# W5500_Ethernet_shield.net
KiCad netlist of a schematic drawn in EAGLE
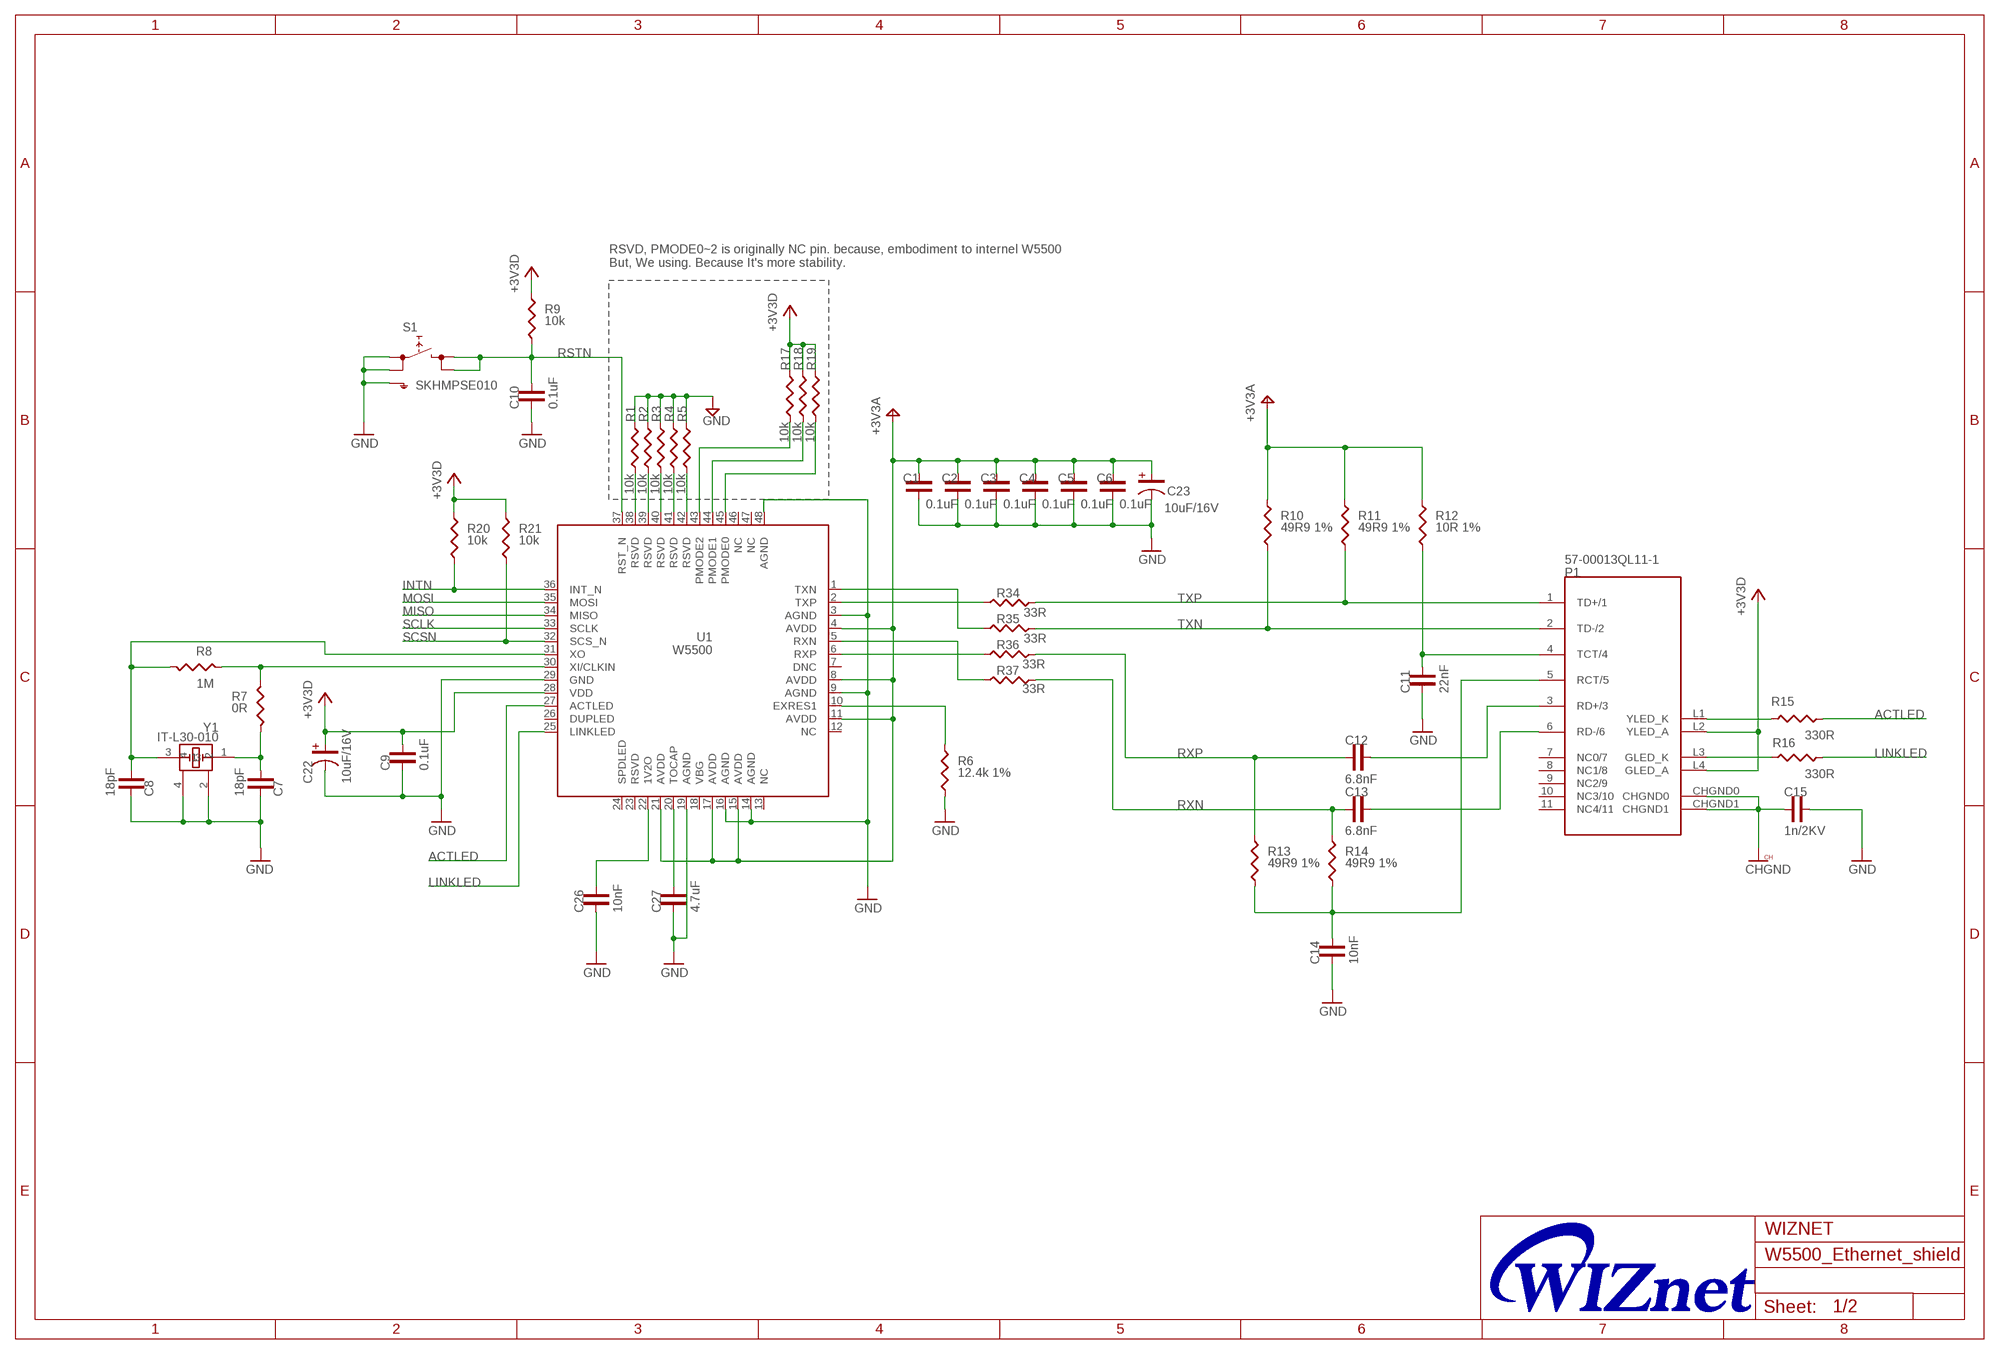
[diagram p0: schematic, sheet 1]
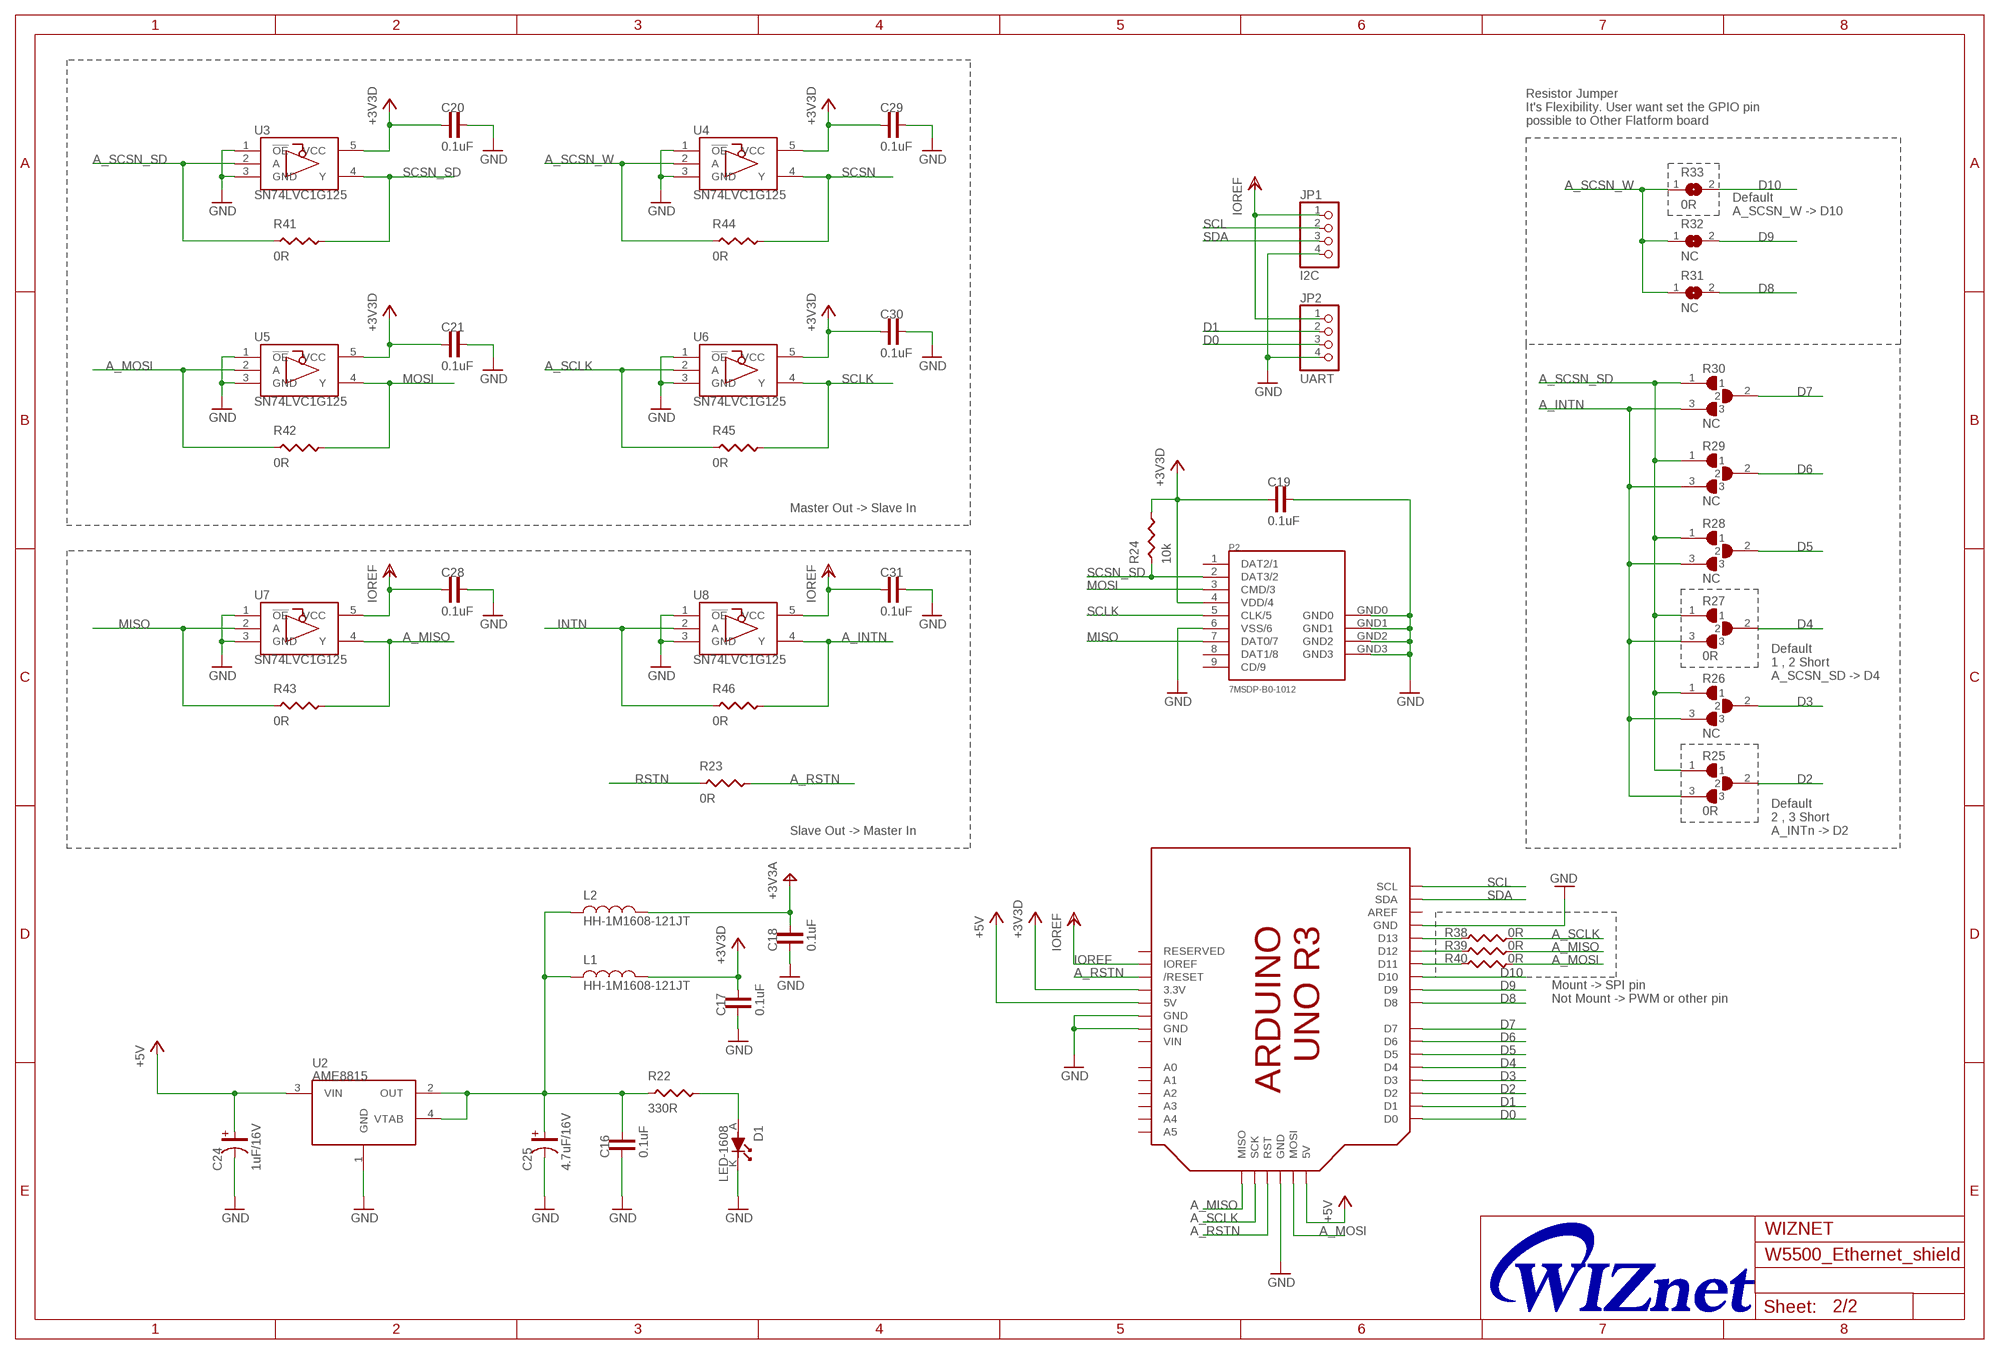
[diagram p1: schematic, sheet 2]

(export (version "E")
  (design (tool "Eeschema 10.0.6"))
  (components
    (comp (ref "C1")
      (value "0.1uF")
      (footprint "eagle-import:C-1608")
      (libsource (lib "eagle-import") (part "C-1608"))
    )
    (comp (ref "C2")
      (value "0.1uF")
      (footprint "eagle-import:C-1608")
      (libsource (lib "eagle-import") (part "C-1608"))
    )
    (comp (ref "C3")
      (value "0.1uF")
      (footprint "eagle-import:C-1608")
      (libsource (lib "eagle-import") (part "C-1608"))
    )
    (comp (ref "C4")
      (value "0.1uF")
      (footprint "eagle-import:C-1608")
      (libsource (lib "eagle-import") (part "C-1608"))
    )
    (comp (ref "C5")
      (value "0.1uF")
      (footprint "eagle-import:C-1608")
      (libsource (lib "eagle-import") (part "C-1608"))
    )
    (comp (ref "C6")
      (value "0.1uF")
      (footprint "eagle-import:C-1608")
      (libsource (lib "eagle-import") (part "C-1608"))
    )
    (comp (ref "C7")
      (value "18pF")
      (footprint "eagle-import:C-1608")
      (libsource (lib "eagle-import") (part "C-1608"))
    )
    (comp (ref "C8")
      (value "18pF")
      (footprint "eagle-import:C-1608")
      (libsource (lib "eagle-import") (part "C-1608"))
    )
    (comp (ref "C9")
      (value "0.1uF")
      (footprint "eagle-import:C-1608")
      (libsource (lib "eagle-import") (part "C-1608"))
    )
    (comp (ref "C10")
      (value "0.1uF")
      (footprint "eagle-import:C-1608")
      (libsource (lib "eagle-import") (part "C-1608"))
    )
    (comp (ref "C11")
      (value "22nF")
      (footprint "eagle-import:C-1608")
      (libsource (lib "eagle-import") (part "C-1608"))
    )
    (comp (ref "C12")
      (value "6.8nF")
      (footprint "eagle-import:C-1608")
      (libsource (lib "eagle-import") (part "C-1608"))
    )
    (comp (ref "C13")
      (value "6.8nF")
      (footprint "eagle-import:C-1608")
      (libsource (lib "eagle-import") (part "C-1608"))
    )
    (comp (ref "C14")
      (value "10nF")
      (footprint "eagle-import:C-1608")
      (libsource (lib "eagle-import") (part "C-1608"))
    )
    (comp (ref "C15")
      (value "1n/2KV")
      (footprint "eagle-import:C-1808")
      (libsource (lib "eagle-import") (part "C-1808"))
    )
    (comp (ref "C22")
      (value "10uF/16V")
      (footprint "eagle-import:C-3216(TANTAL)")
      (libsource (lib "eagle-import") (part "C-3216(TANTAL)"))
    )
    (comp (ref "C23")
      (value "10uF/16V")
      (footprint "eagle-import:C-3216(TANTAL)")
      (libsource (lib "eagle-import") (part "C-3216(TANTAL)"))
    )
    (comp (ref "C26")
      (value "10nF")
      (footprint "eagle-import:C-1608")
      (libsource (lib "eagle-import") (part "C-1608"))
    )
    (comp (ref "C27")
      (value "4.7uF")
      (footprint "eagle-import:C-2012")
      (libsource (lib "eagle-import") (part "C-2012"))
    )
    (comp (ref "P1")
      (value "57-00013QL11-1")
      (footprint "eagle-import:57-00013QL11-1")
      (libsource (lib "eagle-import") (part "57-00013QL11-1"))
    )
    (comp (ref "R1")
      (value "10k")
      (footprint "eagle-import:R-1608")
      (libsource (lib "eagle-import") (part "R-1608"))
    )
    (comp (ref "R2")
      (value "10k")
      (footprint "eagle-import:R-1608")
      (libsource (lib "eagle-import") (part "R-1608"))
    )
    (comp (ref "R3")
      (value "10k")
      (footprint "eagle-import:R-1608")
      (libsource (lib "eagle-import") (part "R-1608"))
    )
    (comp (ref "R4")
      (value "10k")
      (footprint "eagle-import:R-1608")
      (libsource (lib "eagle-import") (part "R-1608"))
    )
    (comp (ref "R5")
      (value "10k")
      (footprint "eagle-import:R-1608")
      (libsource (lib "eagle-import") (part "R-1608"))
    )
    (comp (ref "R6")
      (value "12.4k 1%")
      (footprint "eagle-import:R-1608")
      (libsource (lib "eagle-import") (part "R-1608"))
    )
    (comp (ref "R7")
      (value "0R")
      (footprint "eagle-import:R-1608")
      (libsource (lib "eagle-import") (part "R-1608"))
    )
    (comp (ref "R8")
      (value "1M")
      (footprint "eagle-import:R-1608")
      (libsource (lib "eagle-import") (part "R-1608"))
    )
    (comp (ref "R9")
      (value "10k")
      (footprint "eagle-import:R-1608")
      (libsource (lib "eagle-import") (part "R-1608"))
    )
    (comp (ref "R10")
      (value "49R9 1%")
      (footprint "eagle-import:R-1608")
      (libsource (lib "eagle-import") (part "R-1608"))
    )
    (comp (ref "R11")
      (value "49R9 1%")
      (footprint "eagle-import:R-1608")
      (libsource (lib "eagle-import") (part "R-1608"))
    )
    (comp (ref "R12")
      (value "10R 1%")
      (footprint "eagle-import:R-1608")
      (libsource (lib "eagle-import") (part "R-1608"))
    )
    (comp (ref "R13")
      (value "49R9 1%")
      (footprint "eagle-import:R-1608")
      (libsource (lib "eagle-import") (part "R-1608"))
    )
    (comp (ref "R14")
      (value "49R9 1%")
      (footprint "eagle-import:R-1608")
      (libsource (lib "eagle-import") (part "R-1608"))
    )
    (comp (ref "R15")
      (value "330R")
      (footprint "eagle-import:R-1608")
      (libsource (lib "eagle-import") (part "R-1608"))
    )
    (comp (ref "R16")
      (value "330R")
      (footprint "eagle-import:R-1608")
      (libsource (lib "eagle-import") (part "R-1608"))
    )
    (comp (ref "R17")
      (value "10k")
      (footprint "eagle-import:R-1608")
      (libsource (lib "eagle-import") (part "R-1608"))
    )
    (comp (ref "R18")
      (value "10k")
      (footprint "eagle-import:R-1608")
      (libsource (lib "eagle-import") (part "R-1608"))
    )
    (comp (ref "R19")
      (value "10k")
      (footprint "eagle-import:R-1608")
      (libsource (lib "eagle-import") (part "R-1608"))
    )
    (comp (ref "R20")
      (value "10k")
      (footprint "eagle-import:R-1608")
      (libsource (lib "eagle-import") (part "R-1608"))
    )
    (comp (ref "R21")
      (value "10k")
      (footprint "eagle-import:R-1608")
      (libsource (lib "eagle-import") (part "R-1608"))
    )
    (comp (ref "R34")
      (value "33R")
      (footprint "eagle-import:R-1608")
      (libsource (lib "eagle-import") (part "R-1608"))
    )
    (comp (ref "R35")
      (value "33R")
      (footprint "eagle-import:R-1608")
      (libsource (lib "eagle-import") (part "R-1608"))
    )
    (comp (ref "R36")
      (value "33R")
      (footprint "eagle-import:R-1608")
      (libsource (lib "eagle-import") (part "R-1608"))
    )
    (comp (ref "R37")
      (value "33R")
      (footprint "eagle-import:R-1608")
      (libsource (lib "eagle-import") (part "R-1608"))
    )
    (comp (ref "S1")
      (value "SKHMPSE010")
      (footprint "eagle-import:SKHMPXE010")
      (libsource (lib "eagle-import") (part "SKHMPE010S"))
    )
    (comp (ref "U1")
      (value "W5500")
      (footprint "eagle-import:W5500")
      (libsource (lib "eagle-import") (part "W5500"))
    )
    (comp (ref "Y1")
      (value "IT-L30-010")
      (footprint "eagle-import:IT-L30-010")
      (libsource (lib "eagle-import") (part "IT-L30-010"))
    )
    (comp (ref "C16")
      (value "0.1uF")
      (footprint "eagle-import:C-1608")
      (libsource (lib "eagle-import") (part "C-1608"))
    )
    (comp (ref "C17")
      (value "0.1uF")
      (footprint "eagle-import:C-1608")
      (libsource (lib "eagle-import") (part "C-1608"))
    )
    (comp (ref "C18")
      (value "0.1uF")
      (footprint "eagle-import:C-1608")
      (libsource (lib "eagle-import") (part "C-1608"))
    )
    (comp (ref "C19")
      (value "0.1uF")
      (footprint "eagle-import:C-1608")
      (libsource (lib "eagle-import") (part "C-1608"))
    )
    (comp (ref "C20")
      (value "0.1uF")
      (footprint "eagle-import:C-1608")
      (libsource (lib "eagle-import") (part "C-1608"))
    )
    (comp (ref "C21")
      (value "0.1uF")
      (footprint "eagle-import:C-1608")
      (libsource (lib "eagle-import") (part "C-1608"))
    )
    (comp (ref "C24")
      (value "1uF/16V")
      (footprint "eagle-import:C-3216(TANTAL)")
      (libsource (lib "eagle-import") (part "C-3216(TANTAL)"))
    )
    (comp (ref "C25")
      (value "4.7uF/16V")
      (footprint "eagle-import:C-3216(TANTAL)")
      (libsource (lib "eagle-import") (part "C-3216(TANTAL)"))
    )
    (comp (ref "C28")
      (value "0.1uF")
      (footprint "eagle-import:C-1608")
      (libsource (lib "eagle-import") (part "C-1608"))
    )
    (comp (ref "C29")
      (value "0.1uF")
      (footprint "eagle-import:C-1608")
      (libsource (lib "eagle-import") (part "C-1608"))
    )
    (comp (ref "C30")
      (value "0.1uF")
      (footprint "eagle-import:C-1608")
      (libsource (lib "eagle-import") (part "C-1608"))
    )
    (comp (ref "C31")
      (value "0.1uF")
      (footprint "eagle-import:C-1608")
      (libsource (lib "eagle-import") (part "C-1608"))
    )
    (comp (ref "D1")
      (value "LED-1608")
      (footprint "eagle-import:LED-1608")
      (libsource (lib "eagle-import") (part "LED-1608"))
    )
    (comp (ref "JP1")
      (value "I2C")
      (footprint "eagle-import:1X04")
      (libsource (lib "eagle-import") (part "PINHD-1X4"))
    )
    (comp (ref "JP2")
      (value "UART")
      (footprint "eagle-import:1X04")
      (libsource (lib "eagle-import") (part "PINHD-1X4"))
    )
    (comp (ref "L1")
      (value "HH-1M1608-121JT")
      (footprint "eagle-import:L-1608")
      (libsource (lib "eagle-import") (part "L-1608"))
    )
    (comp (ref "L2")
      (value "HH-1M1608-121JT")
      (footprint "eagle-import:L-1608")
      (libsource (lib "eagle-import") (part "L-1608"))
    )
    (comp (ref "P2")
      (value "7MSDP-B0-1012")
      (footprint "eagle-import:7MSDP-B0-1012")
      (libsource (lib "eagle-import") (part "7MSDP-B0-1012"))
    )
    (comp (ref "R22")
      (value "330R")
      (footprint "eagle-import:R-1608")
      (libsource (lib "eagle-import") (part "R-1608"))
    )
    (comp (ref "R23")
      (value "0R")
      (footprint "eagle-import:R-1608")
      (libsource (lib "eagle-import") (part "R-1608"))
    )
    (comp (ref "R24")
      (value "10k")
      (footprint "eagle-import:R-1608")
      (libsource (lib "eagle-import") (part "R-1608"))
    )
    (comp (ref "R25")
      (value "0R")
      (footprint "eagle-import:RESISTOR_JUMPER_3")
      (libsource (lib "eagle-import") (part "RESISTOR_JUMPER_3"))
    )
    (comp (ref "R26")
      (value "NC")
      (footprint "eagle-import:RESISTOR_JUMPER_3")
      (libsource (lib "eagle-import") (part "RESISTOR_JUMPER_3"))
    )
    (comp (ref "R27")
      (value "0R")
      (footprint "eagle-import:RESISTOR_JUMPER_3")
      (libsource (lib "eagle-import") (part "RESISTOR_JUMPER_3"))
    )
    (comp (ref "R28")
      (value "NC")
      (footprint "eagle-import:RESISTOR_JUMPER_3")
      (libsource (lib "eagle-import") (part "RESISTOR_JUMPER_3"))
    )
    (comp (ref "R29")
      (value "NC")
      (footprint "eagle-import:RESISTOR_JUMPER_3")
      (libsource (lib "eagle-import") (part "RESISTOR_JUMPER_3"))
    )
    (comp (ref "R30")
      (value "NC")
      (footprint "eagle-import:RESISTOR_JUMPER_3")
      (libsource (lib "eagle-import") (part "RESISTOR_JUMPER_3"))
    )
    (comp (ref "R31")
      (value "NC")
      (footprint "eagle-import:SJW")
      (libsource (lib "eagle-import") (part "SJ_2"))
    )
    (comp (ref "R32")
      (value "NC")
      (footprint "eagle-import:SJW")
      (libsource (lib "eagle-import") (part "SJ_2"))
    )
    (comp (ref "R33")
      (value "0R")
      (footprint "eagle-import:SJW")
      (libsource (lib "eagle-import") (part "SJ_2"))
    )
    (comp (ref "R38")
      (value "0R")
      (footprint "eagle-import:R-1608")
      (libsource (lib "eagle-import") (part "R-1608"))
    )
    (comp (ref "R39")
      (value "0R")
      (footprint "eagle-import:R-1608")
      (libsource (lib "eagle-import") (part "R-1608"))
    )
    (comp (ref "R40")
      (value "0R")
      (footprint "eagle-import:R-1608")
      (libsource (lib "eagle-import") (part "R-1608"))
    )
    (comp (ref "R41")
      (value "0R")
      (footprint "eagle-import:R-1608")
      (libsource (lib "eagle-import") (part "R-1608"))
    )
    (comp (ref "R42")
      (value "0R")
      (footprint "eagle-import:R-1608")
      (libsource (lib "eagle-import") (part "R-1608"))
    )
    (comp (ref "R43")
      (value "0R")
      (footprint "eagle-import:R-1608")
      (libsource (lib "eagle-import") (part "R-1608"))
    )
    (comp (ref "R44")
      (value "0R")
      (footprint "eagle-import:R-1608")
      (libsource (lib "eagle-import") (part "R-1608"))
    )
    (comp (ref "R45")
      (value "0R")
      (footprint "eagle-import:R-1608")
      (libsource (lib "eagle-import") (part "R-1608"))
    )
    (comp (ref "R46")
      (value "0R")
      (footprint "eagle-import:R-1608")
      (libsource (lib "eagle-import") (part "R-1608"))
    )
    (comp (ref "U$1")
      (value "ARDUINO_R3_ICSP")
      (footprint "eagle-import:ARDUINOR3_ICSP")
      (libsource (lib "eagle-import") (part "ARDUINO_R3_ICSP"))
    )
    (comp (ref "U2")
      (value "AME8815")
      (footprint "eagle-import:AME8815")
      (libsource (lib "eagle-import") (part "AME8815"))
    )
    (comp (ref "U3")
      (value "SN74LVC1G125")
      (footprint "eagle-import:SN74LVC1G125")
      (libsource (lib "eagle-import") (part "SN74LVC1G125"))
    )
    (comp (ref "U4")
      (value "SN74LVC1G125")
      (footprint "eagle-import:SN74LVC1G125")
      (libsource (lib "eagle-import") (part "SN74LVC1G125"))
    )
    (comp (ref "U5")
      (value "SN74LVC1G125")
      (footprint "eagle-import:SN74LVC1G125")
      (libsource (lib "eagle-import") (part "SN74LVC1G125"))
    )
    (comp (ref "U6")
      (value "SN74LVC1G125")
      (footprint "eagle-import:SN74LVC1G125")
      (libsource (lib "eagle-import") (part "SN74LVC1G125"))
    )
    (comp (ref "U7")
      (value "SN74LVC1G125")
      (footprint "eagle-import:SN74LVC1G125")
      (libsource (lib "eagle-import") (part "SN74LVC1G125"))
    )
    (comp (ref "U8")
      (value "SN74LVC1G125")
      (footprint "eagle-import:SN74LVC1G125")
      (libsource (lib "eagle-import") (part "SN74LVC1G125"))
    )
  )
  (nets
    (net (code "1") (name "+3V3") (class "Default")
      (node (ref "C17") (pin "2") (pinfunction "P$2_2") (pintype "passive"))
      (node (ref "C19") (pin "1") (pinfunction "P$1_1") (pintype "passive"))
      (node (ref "C20") (pin "1") (pinfunction "P$1_1") (pintype "passive"))
      (node (ref "C21") (pin "1") (pinfunction "P$1_1") (pintype "passive"))
      (node (ref "C22") (pin "1") (pinfunction "1_1") (pintype "passive"))
      (node (ref "C29") (pin "1") (pinfunction "P$1_1") (pintype "passive"))
      (node (ref "C30") (pin "1") (pinfunction "P$1_1") (pintype "passive"))
      (node (ref "C9") (pin "2") (pinfunction "P$2_2") (pintype "passive"))
      (node (ref "L1") (pin "P$2") (pinfunction "2_P$2") (pintype "passive"))
      (node (ref "P1") (pin "L2") (pinfunction "YLED_A_L2") (pintype "passive"))
      (node (ref "P1") (pin "L4") (pinfunction "GLED_A_L4") (pintype "passive"))
      (node (ref "P2") (pin "4") (pinfunction "VDD/4_4") (pintype "passive"))
      (node (ref "R17") (pin "2") (pinfunction "P$2_2") (pintype "passive"))
      (node (ref "R18") (pin "2") (pinfunction "P$2_2") (pintype "passive"))
      (node (ref "R19") (pin "2") (pinfunction "P$2_2") (pintype "passive"))
      (node (ref "R20") (pin "2") (pinfunction "P$2_2") (pintype "passive"))
      (node (ref "R21") (pin "2") (pinfunction "P$2_2") (pintype "passive"))
      (node (ref "R24") (pin "2") (pinfunction "P$2_2") (pintype "passive"))
      (node (ref "R9") (pin "2") (pinfunction "P$2_2") (pintype "passive"))
      (node (ref "U$1") (pin "3V") (pinfunction "3.3V_3V") (pintype "passive"))
      (node (ref "U1") (pin "28") (pinfunction "VDD_28") (pintype "passive"))
      (node (ref "U3") (pin "5") (pinfunction "VCC_5") (pintype "passive"))
      (node (ref "U4") (pin "5") (pinfunction "VCC_5") (pintype "passive"))
      (node (ref "U5") (pin "5") (pinfunction "VCC_5") (pintype "passive"))
      (node (ref "U6") (pin "5") (pinfunction "VCC_5") (pintype "passive"))
    )
    (net (code "2") (name "+3V3A") (class "Default")
      (node (ref "C1") (pin "2") (pinfunction "P$2_2") (pintype "passive"))
      (node (ref "C18") (pin "2") (pinfunction "P$2_2") (pintype "passive"))
      (node (ref "C2") (pin "2") (pinfunction "P$2_2") (pintype "passive"))
      (node (ref "C23") (pin "1") (pinfunction "1_1") (pintype "passive"))
      (node (ref "C3") (pin "2") (pinfunction "P$2_2") (pintype "passive"))
      (node (ref "C4") (pin "2") (pinfunction "P$2_2") (pintype "passive"))
      (node (ref "C5") (pin "2") (pinfunction "P$2_2") (pintype "passive"))
      (node (ref "C6") (pin "2") (pinfunction "P$2_2") (pintype "passive"))
      (node (ref "L2") (pin "P$2") (pinfunction "2_P$2") (pintype "passive"))
      (node (ref "R10") (pin "2") (pinfunction "P$2_2") (pintype "passive"))
      (node (ref "R11") (pin "2") (pinfunction "P$2_2") (pintype "passive"))
      (node (ref "R12") (pin "2") (pinfunction "P$2_2") (pintype "passive"))
      (node (ref "U1") (pin "11") (pinfunction "AVDD_11") (pintype "passive"))
      (node (ref "U1") (pin "15") (pinfunction "AVDD_15") (pintype "passive"))
      (node (ref "U1") (pin "17") (pinfunction "AVDD_17") (pintype "passive"))
      (node (ref "U1") (pin "21") (pinfunction "AVDD_21") (pintype "passive"))
      (node (ref "U1") (pin "4") (pinfunction "AVDD_4") (pintype "passive"))
      (node (ref "U1") (pin "8") (pinfunction "AVDD_8") (pintype "passive"))
    )
    (net (code "3") (name "+5V") (class "Default")
      (node (ref "C24") (pin "1") (pinfunction "1_1") (pintype "passive"))
      (node (ref "U$1") (pin "5V") (pinfunction "5V_5V") (pintype "passive"))
      (node (ref "U$1") (pin "5V_ICSP") (pinfunction "5V_5V_ICSP") (pintype "passive"))
      (node (ref "U2") (pin "3") (pinfunction "VIN_3") (pintype "passive"))
    )
    (net (code "4") (name "ACTLED") (class "Default")
      (node (ref "R15") (pin "1") (pinfunction "P$1_1") (pintype "passive"))
      (node (ref "U1") (pin "27") (pinfunction "ACTLED_27") (pintype "passive"))
    )
    (net (code "5") (name "A_INTN") (class "Default")
      (node (ref "R25") (pin "3") (pinfunction "3_3") (pintype "passive"))
      (node (ref "R26") (pin "3") (pinfunction "3_3") (pintype "passive"))
      (node (ref "R27") (pin "3") (pinfunction "3_3") (pintype "passive"))
      (node (ref "R28") (pin "3") (pinfunction "3_3") (pintype "passive"))
      (node (ref "R29") (pin "3") (pinfunction "3_3") (pintype "passive"))
      (node (ref "R30") (pin "3") (pinfunction "3_3") (pintype "passive"))
      (node (ref "R46") (pin "2") (pinfunction "P$2_2") (pintype "passive"))
      (node (ref "U8") (pin "4") (pinfunction "Y_4") (pintype "passive"))
    )
    (net (code "6") (name "A_MISO") (class "Default")
      (node (ref "R39") (pin "2") (pinfunction "P$2_2") (pintype "passive"))
      (node (ref "R43") (pin "2") (pinfunction "P$2_2") (pintype "passive"))
      (node (ref "U$1") (pin "MISO") (pinfunction "MISO_MISO") (pintype "passive"))
      (node (ref "U7") (pin "4") (pinfunction "Y_4") (pintype "passive"))
    )
    (net (code "7") (name "A_MOSI") (class "Default")
      (node (ref "R40") (pin "2") (pinfunction "P$2_2") (pintype "passive"))
      (node (ref "R42") (pin "1") (pinfunction "P$1_1") (pintype "passive"))
      (node (ref "U$1") (pin "MOSI") (pinfunction "MOSI_MOSI") (pintype "passive"))
      (node (ref "U5") (pin "2") (pinfunction "A_2") (pintype "passive"))
    )
    (net (code "8") (name "A_RSTN") (class "Default")
      (node (ref "R23") (pin "2") (pinfunction "P$2_2") (pintype "passive"))
      (node (ref "U$1") (pin "RESET") (pinfunction "/RESET_RESET") (pintype "bidirectional"))
      (node (ref "U$1") (pin "RESET_ICSP") (pinfunction "RST_RESET_ICSP") (pintype "passive"))
    )
    (net (code "9") (name "A_SCLK") (class "Default")
      (node (ref "R38") (pin "2") (pinfunction "P$2_2") (pintype "passive"))
      (node (ref "R45") (pin "1") (pinfunction "P$1_1") (pintype "passive"))
      (node (ref "U$1") (pin "SCK") (pinfunction "SCK_SCK") (pintype "passive"))
      (node (ref "U6") (pin "2") (pinfunction "A_2") (pintype "passive"))
    )
    (net (code "10") (name "A_SCSN_SD") (class "Default")
      (node (ref "R25") (pin "1") (pinfunction "1_1") (pintype "passive"))
      (node (ref "R26") (pin "1") (pinfunction "1_1") (pintype "passive"))
      (node (ref "R27") (pin "1") (pinfunction "1_1") (pintype "passive"))
      (node (ref "R28") (pin "1") (pinfunction "1_1") (pintype "passive"))
      (node (ref "R29") (pin "1") (pinfunction "1_1") (pintype "passive"))
      (node (ref "R30") (pin "1") (pinfunction "1_1") (pintype "passive"))
      (node (ref "R41") (pin "1") (pinfunction "P$1_1") (pintype "passive"))
      (node (ref "U3") (pin "2") (pinfunction "A_2") (pintype "passive"))
    )
    (net (code "11") (name "A_SCSN_W") (class "Default")
      (node (ref "R31") (pin "1") (pinfunction "1_1") (pintype "passive"))
      (node (ref "R32") (pin "1") (pinfunction "1_1") (pintype "passive"))
      (node (ref "R33") (pin "1") (pinfunction "1_1") (pintype "passive"))
      (node (ref "R44") (pin "1") (pinfunction "P$1_1") (pintype "passive"))
      (node (ref "U4") (pin "2") (pinfunction "A_2") (pintype "passive"))
    )
    (net (code "12") (name "CHGND") (class "Default")
      (node (ref "C15") (pin "P$1") (pinfunction "P$1_P$1") (pintype "passive"))
      (node (ref "P1") (pin "CHGND0") (pinfunction "CHGND0_CHGND0") (pintype "passive"))
      (node (ref "P1") (pin "CHGND1") (pinfunction "CHGND1_CHGND1") (pintype "passive"))
    )
    (net (code "13") (name "D0") (class "Default")
      (node (ref "JP2") (pin "3") (pinfunction "3_3") (pintype "passive"))
      (node (ref "U$1") (pin "D0") (pinfunction "D0_D0") (pintype "bidirectional"))
    )
    (net (code "14") (name "D1") (class "Default")
      (node (ref "JP2") (pin "2") (pinfunction "2_2") (pintype "passive"))
      (node (ref "U$1") (pin "D1") (pinfunction "D1_D1") (pintype "bidirectional"))
    )
    (net (code "15") (name "D2") (class "Default")
      (node (ref "R25") (pin "2") (pinfunction "2_2") (pintype "passive"))
      (node (ref "U$1") (pin "D2") (pinfunction "D2_D2") (pintype "bidirectional"))
    )
    (net (code "16") (name "D3") (class "Default")
      (node (ref "R26") (pin "2") (pinfunction "2_2") (pintype "passive"))
      (node (ref "U$1") (pin "D3") (pinfunction "D3_D3") (pintype "bidirectional"))
    )
    (net (code "17") (name "D4") (class "Default")
      (node (ref "R27") (pin "2") (pinfunction "2_2") (pintype "passive"))
      (node (ref "U$1") (pin "D4") (pinfunction "D4_D4") (pintype "bidirectional"))
    )
    (net (code "18") (name "D5") (class "Default")
      (node (ref "R28") (pin "2") (pinfunction "2_2") (pintype "passive"))
      (node (ref "U$1") (pin "D5") (pinfunction "D5_D5") (pintype "bidirectional"))
    )
    (net (code "19") (name "D6") (class "Default")
      (node (ref "R29") (pin "2") (pinfunction "2_2") (pintype "passive"))
      (node (ref "U$1") (pin "D6") (pinfunction "D6_D6") (pintype "bidirectional"))
    )
    (net (code "20") (name "D7") (class "Default")
      (node (ref "R30") (pin "2") (pinfunction "2_2") (pintype "passive"))
      (node (ref "U$1") (pin "D7") (pinfunction "D7_D7") (pintype "bidirectional"))
    )
    (net (code "21") (name "D8") (class "Default")
      (node (ref "R31") (pin "2") (pinfunction "2_2") (pintype "passive"))
      (node (ref "U$1") (pin "D8") (pinfunction "D8_D8") (pintype "bidirectional"))
    )
    (net (code "22") (name "D9") (class "Default")
      (node (ref "R32") (pin "2") (pinfunction "2_2") (pintype "passive"))
      (node (ref "U$1") (pin "D9") (pinfunction "D9_D9") (pintype "bidirectional"))
    )
    (net (code "23") (name "D10") (class "Default")
      (node (ref "R33") (pin "2") (pinfunction "2_2") (pintype "passive"))
      (node (ref "U$1") (pin "D10") (pinfunction "D10_D10") (pintype "bidirectional"))
    )
    (net (code "24") (name "GND") (class "Default")
      (node (ref "C1") (pin "1") (pinfunction "P$1_1") (pintype "passive"))
      (node (ref "C10") (pin "1") (pinfunction "P$1_1") (pintype "passive"))
      (node (ref "C11") (pin "1") (pinfunction "P$1_1") (pintype "passive"))
      (node (ref "C14") (pin "1") (pinfunction "P$1_1") (pintype "passive"))
      (node (ref "C15") (pin "P$2") (pinfunction "P$2_P$2") (pintype "passive"))
      (node (ref "C16") (pin "1") (pinfunction "P$1_1") (pintype "passive"))
      (node (ref "C17") (pin "1") (pinfunction "P$1_1") (pintype "passive"))
      (node (ref "C18") (pin "1") (pinfunction "P$1_1") (pintype "passive"))
      (node (ref "C19") (pin "2") (pinfunction "P$2_2") (pintype "passive"))
      (node (ref "C2") (pin "1") (pinfunction "P$1_1") (pintype "passive"))
      (node (ref "C20") (pin "2") (pinfunction "P$2_2") (pintype "passive"))
      (node (ref "C21") (pin "2") (pinfunction "P$2_2") (pintype "passive"))
      (node (ref "C22") (pin "2") (pinfunction "2_2") (pintype "passive"))
      (node (ref "C23") (pin "2") (pinfunction "2_2") (pintype "passive"))
      (node (ref "C24") (pin "2") (pinfunction "2_2") (pintype "passive"))
      (node (ref "C25") (pin "2") (pinfunction "2_2") (pintype "passive"))
      (node (ref "C26") (pin "1") (pinfunction "P$1_1") (pintype "passive"))
      (node (ref "C27") (pin "P$1") (pinfunction "P$1_P$1") (pintype "passive"))
      (node (ref "C28") (pin "2") (pinfunction "P$2_2") (pintype "passive"))
      (node (ref "C29") (pin "2") (pinfunction "P$2_2") (pintype "passive"))
      (node (ref "C3") (pin "1") (pinfunction "P$1_1") (pintype "passive"))
      (node (ref "C30") (pin "2") (pinfunction "P$2_2") (pintype "passive"))
      (node (ref "C31") (pin "2") (pinfunction "P$2_2") (pintype "passive"))
      (node (ref "C4") (pin "1") (pinfunction "P$1_1") (pintype "passive"))
      (node (ref "C5") (pin "1") (pinfunction "P$1_1") (pintype "passive"))
      (node (ref "C6") (pin "1") (pinfunction "P$1_1") (pintype "passive"))
      (node (ref "C7") (pin "1") (pinfunction "P$1_1") (pintype "passive"))
      (node (ref "C8") (pin "1") (pinfunction "P$1_1") (pintype "passive"))
      (node (ref "C9") (pin "1") (pinfunction "P$1_1") (pintype "passive"))
      (node (ref "D1") (pin "K") (pinfunction "K_K") (pintype "passive"))
      (node (ref "JP1") (pin "4") (pinfunction "4_4") (pintype "passive"))
      (node (ref "JP2") (pin "4") (pinfunction "4_4") (pintype "passive"))
      (node (ref "P2") (pin "6") (pinfunction "VSS/6_6") (pintype "passive"))
      (node (ref "P2") (pin "GND0") (pinfunction "GND0_GND0") (pintype "passive"))
      (node (ref "P2") (pin "GND1") (pinfunction "GND1_GND1") (pintype "passive"))
      (node (ref "P2") (pin "GND2") (pinfunction "GND2_GND2") (pintype "passive"))
      (node (ref "P2") (pin "GND3") (pinfunction "GND3_GND3") (pintype "passive"))
      (node (ref "R1") (pin "2") (pinfunction "P$2_2") (pintype "passive"))
      (node (ref "R2") (pin "2") (pinfunction "P$2_2") (pintype "passive"))
      (node (ref "R3") (pin "2") (pinfunction "P$2_2") (pintype "passive"))
      (node (ref "R4") (pin "2") (pinfunction "P$2_2") (pintype "passive"))
      (node (ref "R5") (pin "2") (pinfunction "P$2_2") (pintype "passive"))
      (node (ref "R6") (pin "1") (pinfunction "P$1_1") (pintype "passive"))
      (node (ref "S1") (pin "1") (pinfunction "1.1_1") (pintype "passive"))
      (node (ref "S1") (pin "2") (pinfunction "1.2_2") (pintype "passive"))
      (node (ref "S1") (pin "5") (pinfunction "SH_5") (pintype "passive"))
      (node (ref "U$1") (pin "GND") (pinfunction "GND_GND") (pintype "power_in"))
      (node (ref "U$1") (pin "GND@1") (pinfunction "GND_GND@1") (pintype "power_in"))
      (node (ref "U$1") (pin "GND@2") (pinfunction "GND_GND@2") (pintype "passive"))
      (node (ref "U$1") (pin "GND@3") (pinfunction "GND_GND@3") (pintype "power_in"))
      (node (ref "U1") (pin "14") (pinfunction "AGND_14") (pintype "passive"))
      (node (ref "U1") (pin "16") (pinfunction "AGND_16") (pintype "passive"))
      (node (ref "U1") (pin "19") (pinfunction "AGND_19") (pintype "passive"))
      (node (ref "U1") (pin "29") (pinfunction "GND_29") (pintype "passive"))
      (node (ref "U1") (pin "3") (pinfunction "AGND_3") (pintype "passive"))
      (node (ref "U1") (pin "48") (pinfunction "AGND_48") (pintype "passive"))
      (node (ref "U1") (pin "9") (pinfunction "AGND_9") (pintype "passive"))
      (node (ref "U2") (pin "1") (pinfunction "GND_1") (pintype "passive"))
      (node (ref "U3") (pin "1") (pinfunction "~{OE}_1") (pintype "passive"))
      (node (ref "U3") (pin "3") (pinfunction "GND_3") (pintype "passive"))
      (node (ref "U4") (pin "1") (pinfunction "~{OE}_1") (pintype "passive"))
      (node (ref "U4") (pin "3") (pinfunction "GND_3") (pintype "passive"))
      (node (ref "U5") (pin "1") (pinfunction "~{OE}_1") (pintype "passive"))
      (node (ref "U5") (pin "3") (pinfunction "GND_3") (pintype "passive"))
      (node (ref "U6") (pin "1") (pinfunction "~{OE}_1") (pintype "passive"))
      (node (ref "U6") (pin "3") (pinfunction "GND_3") (pintype "passive"))
      (node (ref "U7") (pin "1") (pinfunction "~{OE}_1") (pintype "passive"))
      (node (ref "U7") (pin "3") (pinfunction "GND_3") (pintype "passive"))
      (node (ref "U8") (pin "1") (pinfunction "~{OE}_1") (pintype "passive"))
      (node (ref "U8") (pin "3") (pinfunction "GND_3") (pintype "passive"))
      (node (ref "Y1") (pin "2") (pinfunction "2_2") (pintype "passive"))
      (node (ref "Y1") (pin "4") (pinfunction "4_4") (pintype "passive"))
    )
    (net (code "25") (name "INTN") (class "Default")
      (node (ref "R20") (pin "1") (pinfunction "P$1_1") (pintype "passive"))
      (node (ref "R46") (pin "1") (pinfunction "P$1_1") (pintype "passive"))
      (node (ref "U1") (pin "36") (pinfunction "INT_N_36") (pintype "passive"))
      (node (ref "U8") (pin "2") (pinfunction "A_2") (pintype "passive"))
    )
    (net (code "26") (name "IOREF") (class "Default")
      (node (ref "C28") (pin "1") (pinfunction "P$1_1") (pintype "passive"))
      (node (ref "C31") (pin "1") (pinfunction "P$1_1") (pintype "passive"))
      (node (ref "JP1") (pin "1") (pinfunction "1_1") (pintype "passive"))
      (node (ref "JP2") (pin "1") (pinfunction "1_1") (pintype "passive"))
      (node (ref "U$1") (pin "IOREF") (pinfunction "IOREF_IOREF") (pintype "passive"))
      (node (ref "U7") (pin "5") (pinfunction "VCC_5") (pintype "passive"))
      (node (ref "U8") (pin "5") (pinfunction "VCC_5") (pintype "passive"))
    )
    (net (code "27") (name "LINKLED") (class "Default")
      (node (ref "R16") (pin "1") (pinfunction "P$1_1") (pintype "passive"))
      (node (ref "U1") (pin "25") (pinfunction "LINKLED_25") (pintype "passive"))
    )
    (net (code "28") (name "MISO") (class "Default")
      (node (ref "P2") (pin "7") (pinfunction "DAT0/7_7") (pintype "passive"))
      (node (ref "R43") (pin "1") (pinfunction "P$1_1") (pintype "passive"))
      (node (ref "U1") (pin "34") (pinfunction "MISO_34") (pintype "passive"))
      (node (ref "U7") (pin "2") (pinfunction "A_2") (pintype "passive"))
    )
    (net (code "29") (name "MOSI") (class "Default")
      (node (ref "P2") (pin "3") (pinfunction "CMD/3_3") (pintype "passive"))
      (node (ref "R42") (pin "2") (pinfunction "P$2_2") (pintype "passive"))
      (node (ref "U1") (pin "35") (pinfunction "MOSI_35") (pintype "passive"))
      (node (ref "U5") (pin "4") (pinfunction "Y_4") (pintype "passive"))
    )
    (net (code "30") (name "Net-(C7-P$2)") (class "Default")
      (node (ref "C7") (pin "2") (pinfunction "P$2_2") (pintype "passive"))
      (node (ref "R7") (pin "1") (pinfunction "P$1_1") (pintype "passive"))
      (node (ref "Y1") (pin "1") (pinfunction "1_1") (pintype "passive"))
    )
    (net (code "31") (name "Net-(C8-P$2)") (class "Default")
      (node (ref "C8") (pin "2") (pinfunction "P$2_2") (pintype "passive"))
      (node (ref "R8") (pin "1") (pinfunction "P$1_1") (pintype "passive"))
      (node (ref "U1") (pin "31") (pinfunction "XO_31") (pintype "passive"))
      (node (ref "Y1") (pin "3") (pinfunction "3_3") (pintype "passive"))
    )
    (net (code "32") (name "Net-(C11-P$2)") (class "Default")
      (node (ref "C11") (pin "2") (pinfunction "P$2_2") (pintype "passive"))
      (node (ref "P1") (pin "4") (pinfunction "TCT/4_4") (pintype "passive"))
      (node (ref "R12") (pin "1") (pinfunction "P$1_1") (pintype "passive"))
    )
    (net (code "33") (name "Net-(C12-P$2)") (class "Default")
      (node (ref "C12") (pin "2") (pinfunction "P$2_2") (pintype "passive"))
      (node (ref "P1") (pin "3") (pinfunction "RD+/3_3") (pintype "passive"))
    )
    (net (code "34") (name "Net-(C13-P$2)") (class "Default")
      (node (ref "C13") (pin "2") (pinfunction "P$2_2") (pintype "passive"))
      (node (ref "P1") (pin "6") (pinfunction "RD-/6_6") (pintype "passive"))
    )
    (net (code "35") (name "Net-(C14-P$2)") (class "Default")
      (node (ref "C14") (pin "2") (pinfunction "P$2_2") (pintype "passive"))
      (node (ref "P1") (pin "5") (pinfunction "RCT/5_5") (pintype "passive"))
      (node (ref "R13") (pin "1") (pinfunction "P$1_1") (pintype "passive"))
      (node (ref "R14") (pin "1") (pinfunction "P$1_1") (pintype "passive"))
    )
    (net (code "36") (name "Net-(C16-P$2)") (class "Default")
      (node (ref "C16") (pin "2") (pinfunction "P$2_2") (pintype "passive"))
      (node (ref "C25") (pin "1") (pinfunction "1_1") (pintype "passive"))
      (node (ref "L1") (pin "1") (pinfunction "1_1") (pintype "passive"))
      (node (ref "L2") (pin "1") (pinfunction "1_1") (pintype "passive"))
      (node (ref "R22") (pin "1") (pinfunction "P$1_1") (pintype "passive"))
      (node (ref "U2") (pin "2") (pinfunction "OUT_2") (pintype "passive"))
      (node (ref "U2") (pin "4") (pinfunction "VTAB_4") (pintype "passive"))
    )
    (net (code "37") (name "Net-(C26-P$2)") (class "Default")
      (node (ref "C26") (pin "2") (pinfunction "P$2_2") (pintype "passive"))
      (node (ref "U1") (pin "22") (pinfunction "1V2O_22") (pintype "passive"))
    )
    (net (code "38") (name "Net-(P1-GLED_K)") (class "Default")
      (node (ref "P1") (pin "L3") (pinfunction "GLED_K_L3") (pintype "passive"))
      (node (ref "R16") (pin "2") (pinfunction "P$2_2") (pintype "passive"))
    )
    (net (code "39") (name "Net-(P1-YLED_K)") (class "Default")
      (node (ref "P1") (pin "L1") (pinfunction "YLED_K_L1") (pintype "passive"))
      (node (ref "R15") (pin "2") (pinfunction "P$2_2") (pintype "passive"))
    )
    (net (code "40") (name "Net-(R1-P$1)") (class "Default")
      (node (ref "R1") (pin "1") (pinfunction "P$1_1") (pintype "passive"))
      (node (ref "U1") (pin "38") (pinfunction "RSVD_38") (pintype "passive"))
    )
    (net (code "41") (name "Net-(R2-P$1)") (class "Default")
      (node (ref "R2") (pin "1") (pinfunction "P$1_1") (pintype "passive"))
      (node (ref "U1") (pin "39") (pinfunction "RSVD_39") (pintype "passive"))
    )
    (net (code "42") (name "Net-(R3-P$1)") (class "Default")
      (node (ref "R3") (pin "1") (pinfunction "P$1_1") (pintype "passive"))
      (node (ref "U1") (pin "40") (pinfunction "RSVD_40") (pintype "passive"))
    )
    (net (code "43") (name "Net-(R4-P$1)") (class "Default")
      (node (ref "R4") (pin "1") (pinfunction "P$1_1") (pintype "passive"))
      (node (ref "U1") (pin "41") (pinfunction "RSVD_41") (pintype "passive"))
    )
    (net (code "44") (name "Net-(R5-P$1)") (class "Default")
      (node (ref "R5") (pin "1") (pinfunction "P$1_1") (pintype "passive"))
      (node (ref "U1") (pin "42") (pinfunction "RSVD_42") (pintype "passive"))
    )
    (net (code "45") (name "Net-(R6-P$2)") (class "Default")
      (node (ref "R6") (pin "2") (pinfunction "P$2_2") (pintype "passive"))
      (node (ref "U1") (pin "10") (pinfunction "EXRES1_10") (pintype "passive"))
    )
    (net (code "46") (name "Net-(R7-P$2)") (class "Default")
      (node (ref "R7") (pin "2") (pinfunction "P$2_2") (pintype "passive"))
      (node (ref "R8") (pin "2") (pinfunction "P$2_2") (pintype "passive"))
      (node (ref "U1") (pin "30") (pinfunction "XI/CLKIN_30") (pintype "passive"))
    )
    (net (code "47") (name "Net-(R17-P$1)") (class "Default")
      (node (ref "R17") (pin "1") (pinfunction "P$1_1") (pintype "passive"))
      (node (ref "U1") (pin "43") (pinfunction "PMODE2_43") (pintype "passive"))
    )
    (net (code "48") (name "Net-(R18-P$1)") (class "Default")
      (node (ref "R18") (pin "1") (pinfunction "P$1_1") (pintype "passive"))
      (node (ref "U1") (pin "44") (pinfunction "PMODE1_44") (pintype "passive"))
    )
    (net (code "49") (name "Net-(R19-P$1)") (class "Default")
      (node (ref "R19") (pin "1") (pinfunction "P$1_1") (pintype "passive"))
      (node (ref "U1") (pin "45") (pinfunction "PMODE0_45") (pintype "passive"))
    )
    (net (code "50") (name "Net-(R22-P$2)") (class "Default")
      (node (ref "D1") (pin "A") (pinfunction "A_A") (pintype "passive"))
      (node (ref "R22") (pin "2") (pinfunction "P$2_2") (pintype "passive"))
    )
    (net (code "51") (name "Net-(R34-P$2)") (class "Default")
      (node (ref "R34") (pin "2") (pinfunction "P$2_2") (pintype "passive"))
      (node (ref "U1") (pin "2") (pinfunction "TXP_2") (pintype "passive"))
    )
    (net (code "52") (name "Net-(R35-P$2)") (class "Default")
      (node (ref "R35") (pin "2") (pinfunction "P$2_2") (pintype "passive"))
      (node (ref "U1") (pin "1") (pinfunction "TXN_1") (pintype "passive"))
    )
    (net (code "53") (name "Net-(R36-P$2)") (class "Default")
      (node (ref "R36") (pin "2") (pinfunction "P$2_2") (pintype "passive"))
      (node (ref "U1") (pin "6") (pinfunction "RXP_6") (pintype "passive"))
    )
    (net (code "54") (name "Net-(R37-P$2)") (class "Default")
      (node (ref "R37") (pin "2") (pinfunction "P$2_2") (pintype "passive"))
      (node (ref "U1") (pin "5") (pinfunction "RXN_5") (pintype "passive"))
    )
    (net (code "55") (name "Net-(R38-P$1)") (class "Default")
      (node (ref "R38") (pin "1") (pinfunction "P$1_1") (pintype "passive"))
      (node (ref "U$1") (pin "D13") (pinfunction "D13_D13") (pintype "bidirectional"))
    )
    (net (code "56") (name "Net-(R39-P$1)") (class "Default")
      (node (ref "R39") (pin "1") (pinfunction "P$1_1") (pintype "passive"))
      (node (ref "U$1") (pin "D12") (pinfunction "D12_D12") (pintype "bidirectional"))
    )
    (net (code "57") (name "Net-(R40-P$1)") (class "Default")
      (node (ref "R40") (pin "1") (pinfunction "P$1_1") (pintype "passive"))
      (node (ref "U$1") (pin "D11") (pinfunction "D11_D11") (pintype "bidirectional"))
    )
    (net (code "58") (name "Net-(U1-TOCAP)") (class "Default")
      (node (ref "C27") (pin "P$2") (pinfunction "P$2_P$2") (pintype "passive"))
      (node (ref "U1") (pin "20") (pinfunction "TOCAP_20") (pintype "passive"))
    )
    (net (code "59") (name "RSTN") (class "Default")
      (node (ref "C10") (pin "2") (pinfunction "P$2_2") (pintype "passive"))
      (node (ref "R23") (pin "1") (pinfunction "P$1_1") (pintype "passive"))
      (node (ref "R9") (pin "1") (pinfunction "P$1_1") (pintype "passive"))
      (node (ref "S1") (pin "3") (pinfunction "2.1_3") (pintype "passive"))
      (node (ref "S1") (pin "4") (pinfunction "2.2_4") (pintype "passive"))
      (node (ref "U1") (pin "37") (pinfunction "RST_N_37") (pintype "passive"))
    )
    (net (code "60") (name "RXN") (class "Default")
      (node (ref "C13") (pin "1") (pinfunction "P$1_1") (pintype "passive"))
      (node (ref "R14") (pin "2") (pinfunction "P$2_2") (pintype "passive"))
      (node (ref "R37") (pin "1") (pinfunction "P$1_1") (pintype "passive"))
    )
    (net (code "61") (name "RXP") (class "Default")
      (node (ref "C12") (pin "1") (pinfunction "P$1_1") (pintype "passive"))
      (node (ref "R13") (pin "2") (pinfunction "P$2_2") (pintype "passive"))
      (node (ref "R36") (pin "1") (pinfunction "P$1_1") (pintype "passive"))
    )
    (net (code "62") (name "SCL") (class "Default")
      (node (ref "JP1") (pin "2") (pinfunction "2_2") (pintype "passive"))
      (node (ref "U$1") (pin "SCL") (pinfunction "SCL_SCL") (pintype "bidirectional"))
    )
    (net (code "63") (name "SCLK") (class "Default")
      (node (ref "P2") (pin "5") (pinfunction "CLK/5_5") (pintype "passive"))
      (node (ref "R45") (pin "2") (pinfunction "P$2_2") (pintype "passive"))
      (node (ref "U1") (pin "33") (pinfunction "SCLK_33") (pintype "passive"))
      (node (ref "U6") (pin "4") (pinfunction "Y_4") (pintype "passive"))
    )
    (net (code "64") (name "SCSN") (class "Default")
      (node (ref "R21") (pin "1") (pinfunction "P$1_1") (pintype "passive"))
      (node (ref "R44") (pin "2") (pinfunction "P$2_2") (pintype "passive"))
      (node (ref "U1") (pin "32") (pinfunction "SCS_N_32") (pintype "passive"))
      (node (ref "U4") (pin "4") (pinfunction "Y_4") (pintype "passive"))
    )
    (net (code "65") (name "SCSN_SD") (class "Default")
      (node (ref "P2") (pin "2") (pinfunction "DAT3/2_2") (pintype "passive"))
      (node (ref "R24") (pin "1") (pinfunction "P$1_1") (pintype "passive"))
      (node (ref "R41") (pin "2") (pinfunction "P$2_2") (pintype "passive"))
      (node (ref "U3") (pin "4") (pinfunction "Y_4") (pintype "passive"))
    )
    (net (code "66") (name "SDA") (class "Default")
      (node (ref "JP1") (pin "3") (pinfunction "3_3") (pintype "passive"))
      (node (ref "U$1") (pin "SDA") (pinfunction "SDA_SDA") (pintype "bidirectional"))
    )
    (net (code "67") (name "TXN") (class "Default")
      (node (ref "P1") (pin "2") (pinfunction "TD-/2_2") (pintype "passive"))
      (node (ref "R10") (pin "1") (pinfunction "P$1_1") (pintype "passive"))
      (node (ref "R35") (pin "1") (pinfunction "P$1_1") (pintype "passive"))
    )
    (net (code "68") (name "TXP") (class "Default")
      (node (ref "P1") (pin "1") (pinfunction "TD+/1_1") (pintype "passive"))
      (node (ref "R11") (pin "1") (pinfunction "P$1_1") (pintype "passive"))
      (node (ref "R34") (pin "1") (pinfunction "P$1_1") (pintype "passive"))
    )
    (net (code "69") (name "unconnected-(P1-NC0{slash}7-Pad7)") (class "Default")
      (node (ref "P1") (pin "7") (pinfunction "NC0/7_7") (pintype "passive"))
    )
    (net (code "70") (name "unconnected-(P1-NC1{slash}8-Pad8)") (class "Default")
      (node (ref "P1") (pin "8") (pinfunction "NC1/8_8") (pintype "passive"))
    )
    (net (code "71") (name "unconnected-(P1-NC2{slash}9-Pad9)") (class "Default")
      (node (ref "P1") (pin "9") (pinfunction "NC2/9_9") (pintype "passive"))
    )
    (net (code "72") (name "unconnected-(P1-NC3{slash}10-Pad10)") (class "Default")
      (node (ref "P1") (pin "10") (pinfunction "NC3/10_10") (pintype "passive"))
    )
    (net (code "73") (name "unconnected-(P1-NC4{slash}11-Pad11)") (class "Default")
      (node (ref "P1") (pin "11") (pinfunction "NC4/11_11") (pintype "passive"))
    )
    (net (code "74") (name "unconnected-(P2-CD{slash}9-Pad9)") (class "Default")
      (node (ref "P2") (pin "9") (pinfunction "CD/9_9") (pintype "passive"))
    )
    (net (code "75") (name "unconnected-(P2-DAT1{slash}8-Pad8)") (class "Default")
      (node (ref "P2") (pin "8") (pinfunction "DAT1/8_8") (pintype "passive"))
    )
    (net (code "76") (name "unconnected-(P2-DAT2{slash}1-Pad1)") (class "Default")
      (node (ref "P2") (pin "1") (pinfunction "DAT2/1_1") (pintype "passive"))
    )
    (net (code "77") (name "unconnected-(U$1-PadA0)") (class "Default")
      (node (ref "U$1") (pin "A0") (pinfunction "A0_A0") (pintype "bidirectional"))
    )
    (net (code "78") (name "unconnected-(U$1-PadA1)") (class "Default")
      (node (ref "U$1") (pin "A1") (pinfunction "A1_A1") (pintype "bidirectional"))
    )
    (net (code "79") (name "unconnected-(U$1-PadA2)") (class "Default")
      (node (ref "U$1") (pin "A2") (pinfunction "A2_A2") (pintype "bidirectional"))
    )
    (net (code "80") (name "unconnected-(U$1-PadA3)") (class "Default")
      (node (ref "U$1") (pin "A3") (pinfunction "A3_A3") (pintype "bidirectional"))
    )
    (net (code "81") (name "unconnected-(U$1-PadA4)") (class "Default")
      (node (ref "U$1") (pin "A4") (pinfunction "A4_A4") (pintype "bidirectional"))
    )
    (net (code "82") (name "unconnected-(U$1-PadA5)") (class "Default")
      (node (ref "U$1") (pin "A5") (pinfunction "A5_A5") (pintype "bidirectional"))
    )
    (net (code "83") (name "unconnected-(U$1-PadAREF)") (class "Default")
      (node (ref "U$1") (pin "AREF") (pinfunction "AREF_AREF") (pintype "bidirectional"))
    )
    (net (code "84") (name "unconnected-(U$1-PadRESERVED)") (class "Default")
      (node (ref "U$1") (pin "RESERVED") (pinfunction "RESERVED_RESERVED") (pintype "no_connect"))
    )
    (net (code "85") (name "unconnected-(U$1-PadVIN)") (class "Default")
      (node (ref "U$1") (pin "VIN") (pinfunction "VIN_VIN") (pintype "passive"))
    )
    (net (code "86") (name "unconnected-(U1-DNC-Pad7)") (class "Default")
      (node (ref "U1") (pin "7") (pinfunction "DNC_7") (pintype "passive"))
    )
    (net (code "87") (name "unconnected-(U1-DUPLED-Pad26)") (class "Default")
      (node (ref "U1") (pin "26") (pinfunction "DUPLED_26") (pintype "passive"))
    )
    (net (code "88") (name "unconnected-(U1-NC-Pad12)") (class "Default")
      (node (ref "U1") (pin "12") (pinfunction "NC_12") (pintype "passive"))
    )
    (net (code "89") (name "unconnected-(U1-NC-Pad13)") (class "Default")
      (node (ref "U1") (pin "13") (pinfunction "NC_13") (pintype "passive"))
    )
    (net (code "90") (name "unconnected-(U1-NC-Pad46)") (class "Default")
      (node (ref "U1") (pin "46") (pinfunction "NC_46") (pintype "passive"))
    )
    (net (code "91") (name "unconnected-(U1-NC-Pad47)") (class "Default")
      (node (ref "U1") (pin "47") (pinfunction "NC_47") (pintype "passive"))
    )
    (net (code "92") (name "unconnected-(U1-RSVD-Pad23)") (class "Default")
      (node (ref "U1") (pin "23") (pinfunction "RSVD_23") (pintype "passive"))
    )
    (net (code "93") (name "unconnected-(U1-SPDLED-Pad24)") (class "Default")
      (node (ref "U1") (pin "24") (pinfunction "SPDLED_24") (pintype "passive"))
    )
    (net (code "94") (name "unconnected-(U1-VBG-Pad18)") (class "Default")
      (node (ref "U1") (pin "18") (pinfunction "VBG_18") (pintype "passive"))
    )
  )
)
